# Pyr0-Piezo_Direct_Extruder_Board2_1_1.net
KiCad netlist of a schematic drawn in EAGLE
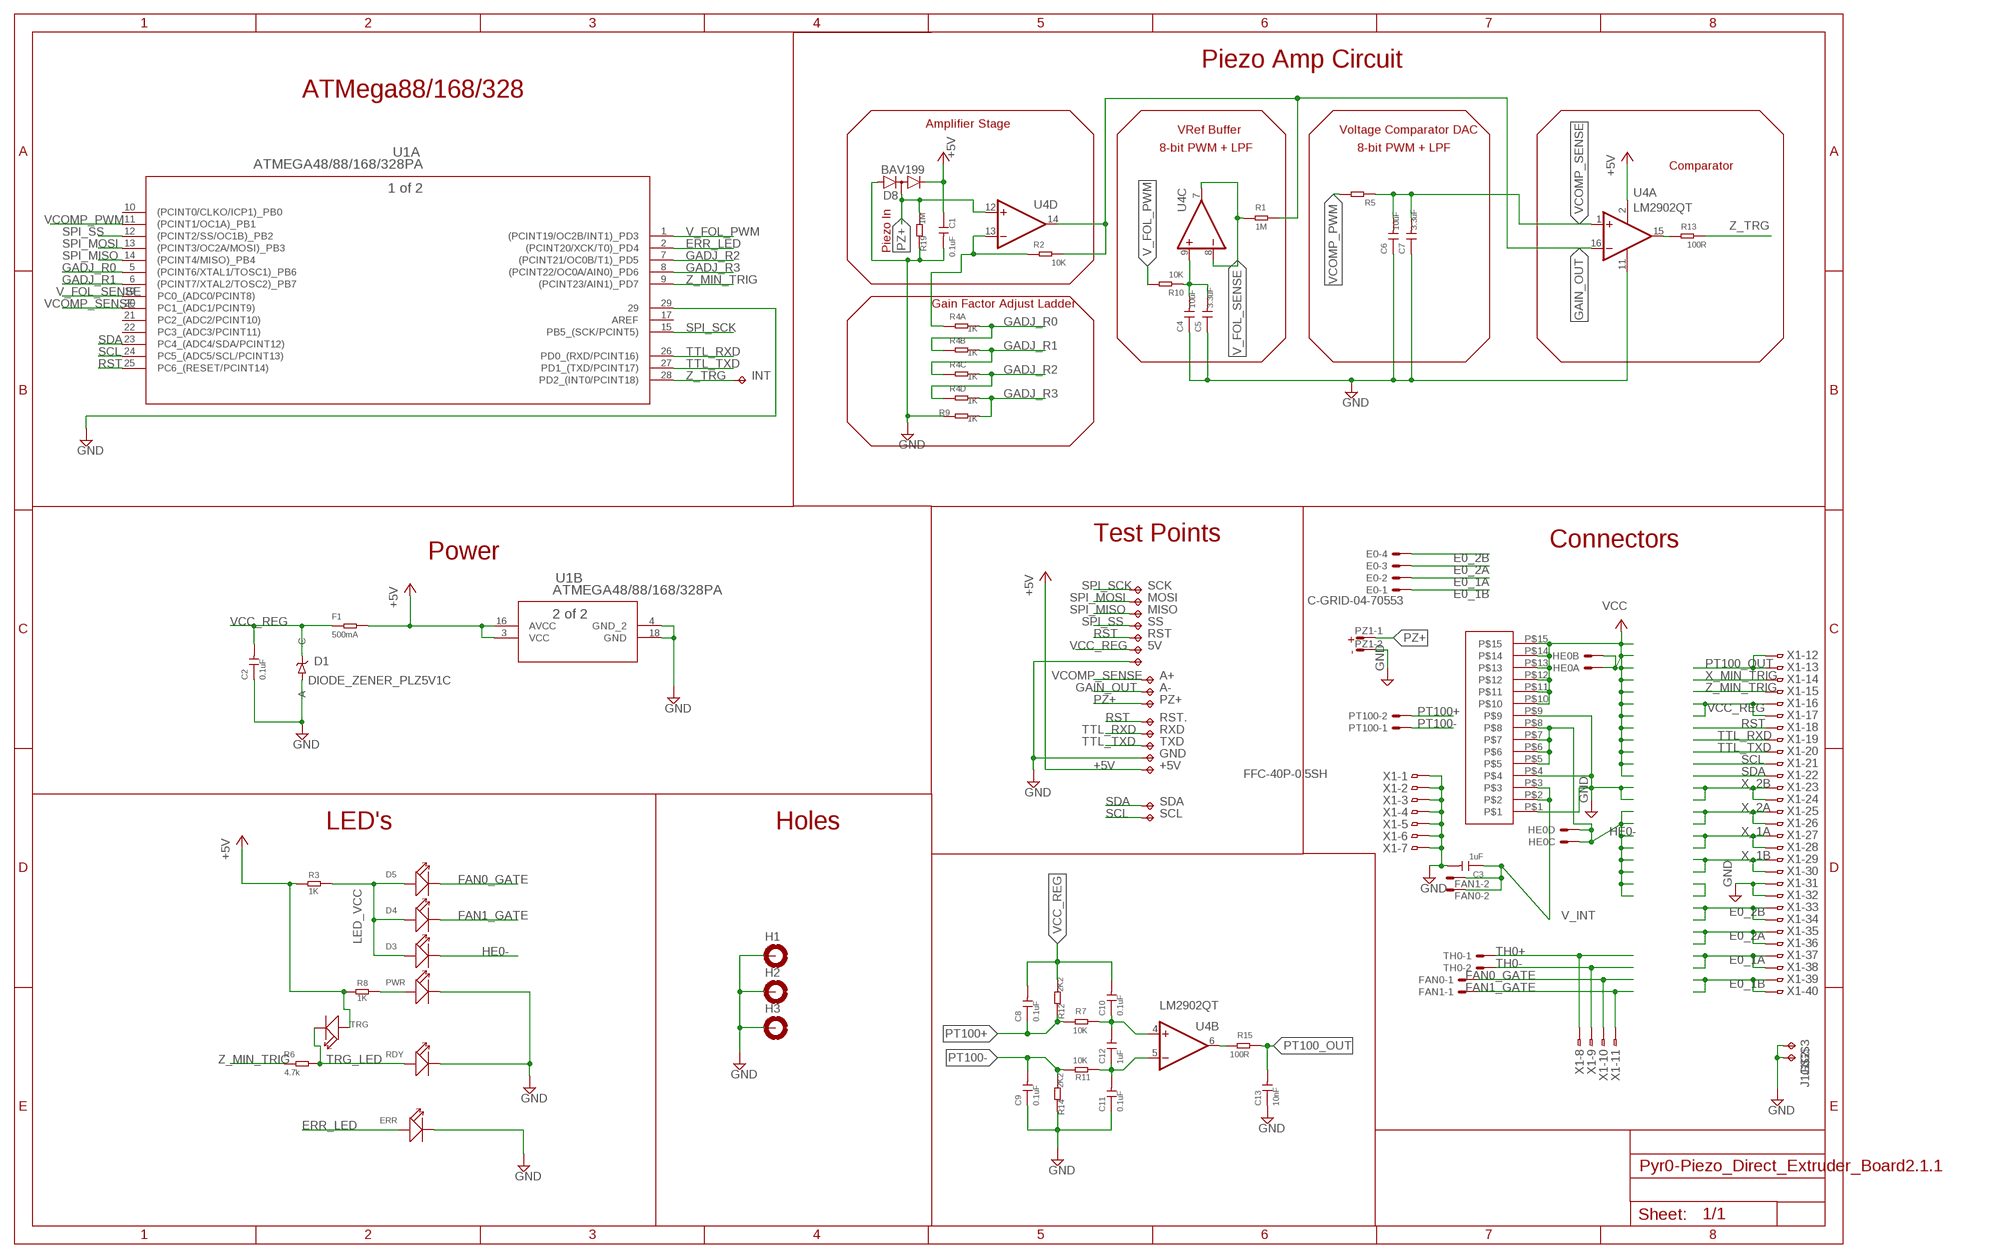
[diagram p0: schematic, sheet 1]

(export (version "E")
  (design (tool "Eeschema 10.0.6"))
  (components
    (comp (ref "+5V")
      (value "TPTP13SQ")
      (footprint "eagle-import:TP13SQ")
      (libsource (lib "eagle-import") (part "testpad_385_TPTP13SQ"))
    )
    (comp (ref "5V")
      (value "TPTP13SQ")
      (footprint "eagle-import:TP13SQ")
      (libsource (lib "eagle-import") (part "TPTP13SQ"))
    )
    (comp (ref "A+")
      (value "TPTP13SQ")
      (footprint "eagle-import:TP13SQ")
      (libsource (lib "eagle-import") (part "TPTP13SQ"))
    )
    (comp (ref "A-")
      (value "TPTP13SQ")
      (footprint "eagle-import:TP13SQ")
      (libsource (lib "eagle-import") (part "TPTP13SQ"))
    )
    (comp (ref "C1")
      (value "0.1uF")
      (footprint "eagle-import:CAPC1005X50")
      (libsource (lib "eagle-import") (part "CERAMIC-1NF-50V-10%-X7R(0402)CAP_0402"))
    )
    (comp (ref "C2")
      (value "0.1uF")
      (footprint "eagle-import:CAPC1005X50")
      (libsource (lib "eagle-import") (part "CERAMIC-1NF-50V-10%-X7R(0402)CAP_0402"))
    )
    (comp (ref "C3")
      (value "1uF")
      (footprint "eagle-import:CAPC1609X80")
      (libsource (lib "eagle-import") (part "SEEED-CAPACITOR_CERAMIC-10UF-25V-10%-X5R(0805)CAP_0603_GEN"))
    )
    (comp (ref "C4")
      (value "10uF")
      (footprint "eagle-import:CAPC1005X50")
      (libsource (lib "eagle-import") (part "CERAMIC-1NF-50V-10%-X7R(0402)CAP_0402"))
    )
    (comp (ref "C5")
      (value "3.3uF")
      (footprint "eagle-import:CAPC1609X80")
      (libsource (lib "eagle-import") (part "SEEED-CAPACITOR_CERAMIC-10UF-25V-10%-X5R(0805)CAP_0603_GEN"))
    )
    (comp (ref "C6")
      (value "10uF")
      (footprint "eagle-import:CAPC1005X50")
      (libsource (lib "eagle-import") (part "CERAMIC-1NF-50V-10%-X7R(0402)CAP_0402"))
    )
    (comp (ref "C7")
      (value "3.3uF")
      (footprint "eagle-import:CAPC1609X80")
      (libsource (lib "eagle-import") (part "SEEED-CAPACITOR_CERAMIC-10UF-25V-10%-X5R(0805)CAP_0603_GEN"))
    )
    (comp (ref "C8")
      (value "0.1uF")
      (footprint "eagle-import:CAPC1005X50")
      (libsource (lib "eagle-import") (part "CERAMIC-1NF-50V-10%-X7R(0402)CAP_0402"))
    )
    (comp (ref "C9")
      (value "0.1uF")
      (footprint "eagle-import:CAPC1005X50")
      (libsource (lib "eagle-import") (part "CERAMIC-1NF-50V-10%-X7R(0402)CAP_0402"))
    )
    (comp (ref "C10")
      (value "0.1uF")
      (footprint "eagle-import:CAPC1005X50")
      (libsource (lib "eagle-import") (part "CERAMIC-1NF-50V-10%-X7R(0402)CAP_0402"))
    )
    (comp (ref "C11")
      (value "0.1uF")
      (footprint "eagle-import:CAPC1005X50")
      (libsource (lib "eagle-import") (part "CERAMIC-1NF-50V-10%-X7R(0402)CAP_0402"))
    )
    (comp (ref "C12")
      (value "1uF")
      (footprint "eagle-import:CAPC1005X50")
      (libsource (lib "eagle-import") (part "CERAMIC-1NF-50V-10%-X7R(0402)CAP_0402"))
    )
    (comp (ref "C13")
      (value "10nF")
      (footprint "eagle-import:CAPC1005X50")
      (libsource (lib "eagle-import") (part "CERAMIC-1NF-50V-10%-X7R(0402)CAP_0402"))
    )
    (comp (ref "D1")
      (value "DIODE_ZENER_PLZ5V1C")
      (footprint "eagle-import:DO-219AC")
      (libsource (lib "eagle-import") (part "DIODE_ZENER_PLZ5V1C"))
    )
    (comp (ref "D3")
      (value "SEEED-LED_SMD-LED-CLEAR-BLUE(0603)LED_0603")
      (footprint "eagle-import:SEEED-LED_LED-0603")
      (libsource (lib "eagle-import") (part "SEEED-LED_SMD-LED-CLEAR-BLUE(0603)LED_0603"))
    )
    (comp (ref "D4")
      (value "SEEED-LED_SMD-LED-CLEAR-BLUE(0603)LED_0603")
      (footprint "eagle-import:SEEED-LED_LED-0603")
      (libsource (lib "eagle-import") (part "SEEED-LED_SMD-LED-CLEAR-BLUE(0603)LED_0603"))
    )
    (comp (ref "D5")
      (value "SEEED-LED_SMD-LED-CLEAR-BLUE(0603)LED_0603")
      (footprint "eagle-import:SEEED-LED_LED-0603")
      (libsource (lib "eagle-import") (part "SEEED-LED_SMD-LED-CLEAR-BLUE(0603)LED_0603"))
    )
    (comp (ref "D8")
      (value "BAV199")
      (footprint "eagle-import:SOT23")
      (libsource (lib "eagle-import") (part "BAV199"))
    )
    (comp (ref "E0")
      (value "C-GRID-04-70553")
      (footprint "eagle-import:70553-04")
      (fields (field (name "MF") "MOLEX"))
      (libsource (lib "eagle-import") (part "C-GRID-04-70553"))
    )
    (comp (ref "ERR")
      (value "SEEED-LED_SMD-LED-CLEAR-BLUE(0603)LED_0603")
      (footprint "eagle-import:SEEED-LED_LED-0603")
      (libsource (lib "eagle-import") (part "SEEED-LED_SMD-LED-CLEAR-BLUE(0603)LED_0603"))
    )
    (comp (ref "F1")
      (value "500mA")
      (footprint "eagle-import:SEEED-RESISTOR_R0603")
      (libsource (lib "eagle-import") (part "SEEED-RESISTOR_SMD-RES-1.5K-1%-1/10W(0603)DETAILED_MODEL"))
    )
    (comp (ref "FAN0")
      (value "CON-MOLEX-2P-1.27MM048")
      (footprint "eagle-import:53048-02")
      (fields (field (name "MF") "MOLEX") (field (name "MPN") "53048-0210"))
      (libsource (lib "eagle-import") (part "CON-MOLEX-2P-1.27MM048"))
    )
    (comp (ref "FAN1")
      (value "CON-MOLEX-2P-1.27MM048")
      (footprint "eagle-import:53048-02")
      (fields (field (name "MF") "MOLEX") (field (name "MPN") "53048-0210"))
      (libsource (lib "eagle-import") (part "CON-MOLEX-2P-1.27MM048"))
    )
    (comp (ref "GND")
      (value "TPTP13SQ")
      (footprint "eagle-import:TP13SQ")
      (libsource (lib "eagle-import") (part "testpad_385_TPTP13SQ"))
    )
    (comp (ref "H1")
      (value "HOLES_MOUNT-PAD-ROUND3.2")
      (footprint "eagle-import:HOLES_3,2-PAD")
      (libsource (lib "eagle-import") (part "HOLES_MOUNT-PAD-ROUND3.2"))
    )
    (comp (ref "H2")
      (value "HOLES_MOUNT-PAD-ROUND3.2")
      (footprint "eagle-import:HOLES_3,2-PAD")
      (libsource (lib "eagle-import") (part "HOLES_MOUNT-PAD-ROUND3.2"))
    )
    (comp (ref "H3")
      (value "HOLES_MOUNT-PAD-ROUND3.2")
      (footprint "eagle-import:HOLES_3,2-PAD")
      (libsource (lib "eagle-import") (part "HOLES_MOUNT-PAD-ROUND3.2"))
    )
    (comp (ref "HE0")
      (value "JST-2.54-2X2JST-DUPONT-2.54-2X2")
      (footprint "eagle-import:HDRRAR4W64P254_2X2_556X736X556B")
      (libsource (lib "eagle-import") (part "JST-2.54-2X2JST-DUPONT-2.54-2X2"))
    )
    (comp (ref "INT")
      (value "TPTP06R")
      (footprint "eagle-import:TP06R")
      (libsource (lib "eagle-import") (part "testpad_385_TPTP06R"))
    )
    (comp (ref "J1")
      (value "FFC-15P-1MM")
      (footprint "eagle-import:FFC-15P-1MM")
      (libsource (lib "eagle-import") (part "FFC-15P-1MM"))
    )
    (comp (ref "MISO")
      (value "TPTP13SQ")
      (footprint "eagle-import:TP13SQ")
      (libsource (lib "eagle-import") (part "TPTP13SQ"))
    )
    (comp (ref "MOSI")
      (value "TPTP13SQ")
      (footprint "eagle-import:TP13SQ")
      (libsource (lib "eagle-import") (part "TPTP13SQ"))
    )
    (comp (ref "PT100")
      (value "CON-MOLEX-2P-1.27MM048")
      (footprint "eagle-import:53048-02")
      (fields (field (name "MF") "MOLEX") (field (name "MPN") "53048-0210"))
      (libsource (lib "eagle-import") (part "CON-MOLEX-2P-1.27MM048"))
    )
    (comp (ref "PWR")
      (value "SEEED-LED_SMD-LED-CLEAR-BLUE(0603)LED_0603")
      (footprint "eagle-import:SEEED-LED_LED-0603")
      (libsource (lib "eagle-import") (part "SEEED-LED_SMD-LED-CLEAR-BLUE(0603)LED_0603"))
    )
    (comp (ref "PZ+")
      (value "TPTP13SQ")
      (footprint "eagle-import:TP13SQ")
      (libsource (lib "eagle-import") (part "TPTP13SQ"))
    )
    (comp (ref "PZ1")
      (value "CON-MOLEX-2P-1.27MM048")
      (footprint "eagle-import:53048-02")
      (fields (field (name "MF") "MOLEX") (field (name "MPN") "53048-0210"))
      (libsource (lib "eagle-import") (part "CON-MOLEX-2P-1.27MM048"))
    )
    (comp (ref "R1")
      (value "1M")
      (footprint "eagle-import:R0402")
      (fields (field (name "MPN") "RC0402JR-070RL"))
      (libsource (lib "eagle-import") (part "SMD-RES-0R-5%-1/16W(0402)"))
    )
    (comp (ref "R2")
      (value "10K")
      (footprint "eagle-import:R0402")
      (fields (field (name "MPN") "RC0402JR-070RL"))
      (libsource (lib "eagle-import") (part "SMD-RES-0R-5%-1/16W(0402)"))
    )
    (comp (ref "R3")
      (value "1K")
      (footprint "eagle-import:R0402")
      (fields (field (name "MPN") "RC0402JR-070RL"))
      (libsource (lib "eagle-import") (part "SMD-RES-0R-5%-1/16W(0402)"))
    )
    (comp (ref "R4")
      (value "1K")
      (footprint "eagle-import:EXBN8V")
      (libsource (lib "eagle-import") (part "RESISTOR_NETWORK_X40804"))
    )
    (comp (ref "R5")
      (value "10K")
      (footprint "eagle-import:SEEED-RESISTOR_R0603")
      (libsource (lib "eagle-import") (part "SEEED-RESISTOR_SMD-RES-1.5K-1%-1/10W(0603)DETAILED_MODEL"))
    )
    (comp (ref "R6")
      (value "4.7k")
      (footprint "eagle-import:R0402")
      (fields (field (name "MPN") "RC0402JR-070RL"))
      (libsource (lib "eagle-import") (part "SMD-RES-0R-5%-1/16W(0402)"))
    )
    (comp (ref "R7")
      (value "10K")
      (footprint "eagle-import:R0402")
      (fields (field (name "MPN") "RC0402JR-070RL"))
      (libsource (lib "eagle-import") (part "SMD-RES-0R-5%-1/16W(0402)"))
    )
    (comp (ref "R8")
      (value "1K")
      (footprint "eagle-import:R0402")
      (fields (field (name "MPN") "RC0402JR-070RL"))
      (libsource (lib "eagle-import") (part "SMD-RES-0R-5%-1/16W(0402)"))
    )
    (comp (ref "R9")
      (value "1K")
      (footprint "eagle-import:R0402")
      (fields (field (name "MPN") "RC0402JR-070RL"))
      (libsource (lib "eagle-import") (part "SMD-RES-0R-5%-1/16W(0402)"))
    )
    (comp (ref "R10")
      (value "10K")
      (footprint "eagle-import:R0402")
      (fields (field (name "MPN") "RC0402JR-070RL"))
      (libsource (lib "eagle-import") (part "SMD-RES-0R-5%-1/16W(0402)"))
    )
    (comp (ref "R11")
      (value "10K")
      (footprint "eagle-import:R0402")
      (fields (field (name "MPN") "RC0402JR-070RL"))
      (libsource (lib "eagle-import") (part "SMD-RES-0R-5%-1/16W(0402)"))
    )
    (comp (ref "R12")
      (value "2K2")
      (footprint "eagle-import:R0402")
      (fields (field (name "MPN") "RC0402JR-070RL"))
      (libsource (lib "eagle-import") (part "SMD-RES-0R-5%-1/16W(0402)"))
    )
    (comp (ref "R13")
      (value "100R")
      (footprint "eagle-import:R0402")
      (fields (field (name "MPN") "RC0402JR-070RL"))
      (libsource (lib "eagle-import") (part "SMD-RES-0R-5%-1/16W(0402)"))
    )
    (comp (ref "R14")
      (value "2K2")
      (footprint "eagle-import:R0402")
      (fields (field (name "MPN") "RC0402JR-070RL"))
      (libsource (lib "eagle-import") (part "SMD-RES-0R-5%-1/16W(0402)"))
    )
    (comp (ref "R15")
      (value "100R")
      (footprint "eagle-import:R0402")
      (fields (field (name "MPN") "RC0402JR-070RL"))
      (libsource (lib "eagle-import") (part "SMD-RES-0R-5%-1/16W(0402)"))
    )
    (comp (ref "R19")
      (value "1M")
      (footprint "eagle-import:R0402")
      (fields (field (name "MPN") "RC0402JR-070RL"))
      (libsource (lib "eagle-import") (part "SMD-RES-0R-5%-1/16W(0402)"))
    )
    (comp (ref "RDY")
      (value "SEEED-LED_SMD-LED-CLEAR-BLUE(0603)LED_0603")
      (footprint "eagle-import:SEEED-LED_LED-0603")
      (libsource (lib "eagle-import") (part "SEEED-LED_SMD-LED-CLEAR-BLUE(0603)LED_0603"))
    )
    (comp (ref "RST")
      (value "TPTP13SQ")
      (footprint "eagle-import:TP13SQ")
      (libsource (lib "eagle-import") (part "TPTP13SQ"))
    )
    (comp (ref "RST.")
      (value "TPTP13SQ")
      (footprint "eagle-import:TP13SQ")
      (libsource (lib "eagle-import") (part "testpad_385_TPTP13SQ"))
    )
    (comp (ref "RXD")
      (value "TPTP13SQ")
      (footprint "eagle-import:TP13SQ")
      (libsource (lib "eagle-import") (part "testpad_385_TPTP13SQ"))
    )
    (comp (ref "SCK")
      (value "TPTP13SQ")
      (footprint "eagle-import:TP13SQ")
      (libsource (lib "eagle-import") (part "TPTP13SQ"))
    )
    (comp (ref "SCL")
      (value "TPTP13SQ")
      (footprint "eagle-import:TP13SQ")
      (libsource (lib "eagle-import") (part "testpad_385_TPTP13SQ"))
    )
    (comp (ref "SDA")
      (value "TPTP13SQ")
      (footprint "eagle-import:TP13SQ")
      (libsource (lib "eagle-import") (part "testpad_385_TPTP13SQ"))
    )
    (comp (ref "SS")
      (value "TPTP06R")
      (footprint "eagle-import:TP06R")
      (libsource (lib "eagle-import") (part "testpad_385_TPTP06R"))
    )
    (comp (ref "TH0")
      (value "CON-MOLEX-2P-1.27MM048")
      (footprint "eagle-import:53048-02")
      (fields (field (name "MF") "MOLEX") (field (name "MPN") "53048-0210"))
      (libsource (lib "eagle-import") (part "CON-MOLEX-2P-1.27MM048"))
    )
    (comp (ref "TRG")
      (value "SEEED-LED_SMD-LED-CLEAR-BLUE(0603)LED_0603")
      (footprint "eagle-import:SEEED-LED_LED-0603")
      (libsource (lib "eagle-import") (part "SEEED-LED_SMD-LED-CLEAR-BLUE(0603)LED_0603"))
    )
    (comp (ref "TXD")
      (value "TPTP13SQ")
      (footprint "eagle-import:TP13SQ")
      (libsource (lib "eagle-import") (part "testpad_385_TPTP13SQ"))
    )
    (comp (ref "U1")
      (value "ATMEGA48/88/168/328PA")
      (footprint "eagle-import:28M1")
      (fields (field (name "MANUFACTURER_PART_NUMBER") "ATMEGA48PAMMHR"))
      (libsource (lib "eagle-import") (part "ATMEGA48/88/168/328PA"))
    )
    (comp (ref "U4")
      (value "LM2902QT")
      (footprint "eagle-import:QFN16")
      (libsource (lib "eagle-import") (part "LM2902QT"))
    )
    (comp (ref "X1")
      (value "FFC-40P-0.5SH")
      (footprint "eagle-import:FH12-40S-0.5SH")
      (fields (field (name "MPN") "FH12-40S-0.5SH(55)"))
      (libsource (lib "eagle-import") (part "FFC-40P-0.5SH"))
    )
    (comp (ref "⏚")
      (value "TPTP13SQ")
      (footprint "eagle-import:TP13SQ")
      (libsource (lib "eagle-import") (part "testpad_385_TPTP13SQ"))
    )
  )
  (nets
    (net (code "1") (name "+5V") (class "Default")
      (node (ref "+5V") (pin "TP") (pinfunction "TP_TP") (pintype "input"))
      (node (ref "C1") (pin "1") (pinfunction "1_1") (pintype "passive"))
      (node (ref "D8") (pin "2") (pinfunction "C_2") (pintype "passive"))
      (node (ref "F1") (pin "2") (pinfunction "2_2") (pintype "passive"))
      (node (ref "R3") (pin "1") (pinfunction "1_1") (pintype "passive"))
      (node (ref "R8") (pin "1") (pinfunction "1_1") (pintype "passive"))
      (node (ref "TRG") (pin "+") (pinfunction "+_+") (pintype "passive"))
      (node (ref "U1") (pin "16") (pinfunction "AVCC_16") (pintype "power_in"))
      (node (ref "U1") (pin "3") (pinfunction "VCC_3") (pintype "power_in"))
      (node (ref "U4") (pin "2") (pinfunction "V+_2") (pintype "power_in"))
    )
    (net (code "2") (name "/E0_1A") (class "Default")
      (node (ref "E0") (pin "2") (pinfunction "S_2") (pintype "passive"))
      (node (ref "X1") (pin "37") (pinfunction "1_37") (pintype "passive"))
      (node (ref "X1") (pin "38") (pinfunction "1_38") (pintype "passive"))
    )
    (net (code "3") (name "/E0_1B") (class "Default")
      (node (ref "E0") (pin "1") (pinfunction "S_1") (pintype "passive"))
      (node (ref "X1") (pin "39") (pinfunction "1_39") (pintype "passive"))
      (node (ref "X1") (pin "40") (pinfunction "1_40") (pintype "passive"))
    )
    (net (code "4") (name "/E0_2A") (class "Default")
      (node (ref "E0") (pin "3") (pinfunction "S_3") (pintype "passive"))
      (node (ref "X1") (pin "35") (pinfunction "1_35") (pintype "passive"))
      (node (ref "X1") (pin "36") (pinfunction "1_36") (pintype "passive"))
    )
    (net (code "5") (name "/E0_2B") (class "Default")
      (node (ref "E0") (pin "4") (pinfunction "S_4") (pintype "passive"))
      (node (ref "X1") (pin "33") (pinfunction "1_33") (pintype "passive"))
      (node (ref "X1") (pin "34") (pinfunction "1_34") (pintype "passive"))
    )
    (net (code "6") (name "/ERR_LED") (class "Default")
      (node (ref "ERR") (pin "+") (pinfunction "+_+") (pintype "passive"))
      (node (ref "U1") (pin "2") (pinfunction "(PCINT20/XCK/T0)_PD4_2") (pintype "bidirectional"))
    )
    (net (code "7") (name "/FAN0_GATE") (class "Default")
      (node (ref "D5") (pin "-") (pinfunction "-_-") (pintype "passive"))
      (node (ref "FAN0") (pin "1") (pinfunction "S_1") (pintype "passive"))
      (node (ref "X1") (pin "10") (pinfunction "1_10") (pintype "passive"))
    )
    (net (code "8") (name "/FAN1_GATE") (class "Default")
      (node (ref "D4") (pin "-") (pinfunction "-_-") (pintype "passive"))
      (node (ref "FAN1") (pin "1") (pinfunction "S_1") (pintype "passive"))
      (node (ref "X1") (pin "11") (pinfunction "1_11") (pintype "passive"))
    )
    (net (code "9") (name "/GADJ_R0") (class "Default")
      (node (ref "R4") (pin "2") (pinfunction "1_2") (pintype "passive"))
      (node (ref "R4") (pin "8") (pinfunction "2_8") (pintype "passive"))
      (node (ref "U1") (pin "5") (pinfunction "(PCINT6/XTAL1/TOSC1)_PB6_5") (pintype "bidirectional"))
    )
    (net (code "10") (name "/GADJ_R1") (class "Default")
      (node (ref "R4") (pin "3") (pinfunction "1_3") (pintype "passive"))
      (node (ref "R4") (pin "7") (pinfunction "2_7") (pintype "passive"))
      (node (ref "U1") (pin "6") (pinfunction "(PCINT7/XTAL2/TOSC2)_PB7_6") (pintype "bidirectional"))
    )
    (net (code "11") (name "/GADJ_R2") (class "Default")
      (node (ref "R4") (pin "4") (pinfunction "1_4") (pintype "passive"))
      (node (ref "R4") (pin "6") (pinfunction "2_6") (pintype "passive"))
      (node (ref "U1") (pin "7") (pinfunction "(PCINT21/OC0B/T1)_PD5_7") (pintype "bidirectional"))
    )
    (net (code "12") (name "/GADJ_R3") (class "Default")
      (node (ref "R4") (pin "5") (pinfunction "2_5") (pintype "passive"))
      (node (ref "R9") (pin "2") (pinfunction "2_2") (pintype "passive"))
      (node (ref "U1") (pin "8") (pinfunction "(PCINT22/OC0A/AIN0)_PD6_8") (pintype "bidirectional"))
    )
    (net (code "13") (name "/HE0-") (class "Default")
      (node (ref "D3") (pin "-") (pinfunction "-_-") (pintype "passive"))
      (node (ref "HE0") (pin "3") (pinfunction "S_3") (pintype "passive"))
      (node (ref "HE0") (pin "4") (pinfunction "S_4") (pintype "passive"))
      (node (ref "J1") (pin "P$5") (pinfunction "P$5_P$5") (pintype "bidirectional"))
      (node (ref "J1") (pin "P$6") (pinfunction "P$6_P$6") (pintype "bidirectional"))
      (node (ref "J1") (pin "P$7") (pinfunction "P$7_P$7") (pintype "bidirectional"))
      (node (ref "J1") (pin "P$8") (pinfunction "P$8_P$8") (pintype "bidirectional"))
    )
    (net (code "14") (name "/LED_VCC") (class "Default")
      (node (ref "D3") (pin "+") (pinfunction "+_+") (pintype "passive"))
      (node (ref "D4") (pin "+") (pinfunction "+_+") (pintype "passive"))
      (node (ref "D5") (pin "+") (pinfunction "+_+") (pintype "passive"))
      (node (ref "R3") (pin "2") (pinfunction "2_2") (pintype "passive"))
    )
    (net (code "15") (name "/RST") (class "Default")
      (node (ref "RST") (pin "TP") (pinfunction "TP_TP") (pintype "input"))
      (node (ref "RST.") (pin "TP") (pinfunction "TP_TP") (pintype "input"))
      (node (ref "U1") (pin "25") (pinfunction "PC6_(RESET/PCINT14)_25") (pintype "bidirectional"))
      (node (ref "X1") (pin "18") (pinfunction "1_18") (pintype "passive"))
    )
    (net (code "16") (name "/SCL") (class "Default")
      (node (ref "SCL") (pin "TP") (pinfunction "TP_TP") (pintype "input"))
      (node (ref "U1") (pin "24") (pinfunction "PC5_(ADC5/SCL/PCINT13)_24") (pintype "bidirectional"))
      (node (ref "X1") (pin "21") (pinfunction "1_21") (pintype "passive"))
    )
    (net (code "17") (name "/SDA") (class "Default")
      (node (ref "SDA") (pin "TP") (pinfunction "TP_TP") (pintype "input"))
      (node (ref "U1") (pin "23") (pinfunction "PC4_(ADC4/SDA/PCINT12)_23") (pintype "bidirectional"))
      (node (ref "X1") (pin "22") (pinfunction "1_22") (pintype "passive"))
    )
    (net (code "18") (name "/SPI_MISO") (class "Default")
      (node (ref "MISO") (pin "TP") (pinfunction "TP_TP") (pintype "input"))
      (node (ref "U1") (pin "14") (pinfunction "(PCINT4/MISO)_PB4_14") (pintype "bidirectional"))
    )
    (net (code "19") (name "/SPI_MOSI") (class "Default")
      (node (ref "MOSI") (pin "TP") (pinfunction "TP_TP") (pintype "input"))
      (node (ref "U1") (pin "13") (pinfunction "(PCINT3/OC2A/MOSI)_PB3_13") (pintype "bidirectional"))
    )
    (net (code "20") (name "/SPI_SCK") (class "Default")
      (node (ref "SCK") (pin "TP") (pinfunction "TP_TP") (pintype "input"))
      (node (ref "U1") (pin "15") (pinfunction "PB5_(SCK/PCINT5)_15") (pintype "bidirectional"))
    )
    (net (code "21") (name "/SPI_SS") (class "Default")
      (node (ref "SS") (pin "TP") (pinfunction "TP_TP") (pintype "input"))
      (node (ref "U1") (pin "12") (pinfunction "(PCINT2/SS/OC1B)_PB2_12") (pintype "bidirectional"))
    )
    (net (code "22") (name "/TH0+") (class "Default")
      (node (ref "TH0") (pin "1") (pinfunction "S_1") (pintype "passive"))
      (node (ref "X1") (pin "8") (pinfunction "1_8") (pintype "passive"))
    )
    (net (code "23") (name "/TH0-") (class "Default")
      (node (ref "TH0") (pin "2") (pinfunction "S_2") (pintype "passive"))
      (node (ref "X1") (pin "9") (pinfunction "1_9") (pintype "passive"))
    )
    (net (code "24") (name "/TRG_LED") (class "Default")
      (node (ref "R6") (pin "2") (pinfunction "2_2") (pintype "passive"))
      (node (ref "RDY") (pin "+") (pinfunction "+_+") (pintype "passive"))
      (node (ref "TRG") (pin "-") (pinfunction "-_-") (pintype "passive"))
    )
    (net (code "25") (name "/TTL_RXD") (class "Default")
      (node (ref "RXD") (pin "TP") (pinfunction "TP_TP") (pintype "input"))
      (node (ref "U1") (pin "26") (pinfunction "PD0_(RXD/PCINT16)_26") (pintype "bidirectional"))
      (node (ref "X1") (pin "19") (pinfunction "1_19") (pintype "passive"))
    )
    (net (code "26") (name "/TTL_TXD") (class "Default")
      (node (ref "TXD") (pin "TP") (pinfunction "TP_TP") (pintype "input"))
      (node (ref "U1") (pin "27") (pinfunction "PD1_(TXD/PCINT17)_27") (pintype "bidirectional"))
      (node (ref "X1") (pin "20") (pinfunction "1_20") (pintype "passive"))
    )
    (net (code "27") (name "/V_INT") (class "Default")
      (node (ref "C3") (pin "1") (pinfunction "1_1") (pintype "passive"))
      (node (ref "FAN0") (pin "2") (pinfunction "S_2") (pintype "passive"))
      (node (ref "FAN1") (pin "2") (pinfunction "S_2") (pintype "passive"))
      (node (ref "J1") (pin "P$2") (pinfunction "P$2_P$2") (pintype "bidirectional"))
      (node (ref "J1") (pin "P$3") (pinfunction "P$3_P$3") (pintype "bidirectional"))
    )
    (net (code "28") (name "/X_1A") (class "Default")
      (node (ref "X1") (pin "27") (pinfunction "1_27") (pintype "passive"))
      (node (ref "X1") (pin "28") (pinfunction "1_28") (pintype "passive"))
    )
    (net (code "29") (name "/X_1B") (class "Default")
      (node (ref "X1") (pin "29") (pinfunction "1_29") (pintype "passive"))
      (node (ref "X1") (pin "30") (pinfunction "1_30") (pintype "passive"))
    )
    (net (code "30") (name "/X_2A") (class "Default")
      (node (ref "X1") (pin "25") (pinfunction "1_25") (pintype "passive"))
      (node (ref "X1") (pin "26") (pinfunction "1_26") (pintype "passive"))
    )
    (net (code "31") (name "/X_2B") (class "Default")
      (node (ref "X1") (pin "23") (pinfunction "1_23") (pintype "passive"))
      (node (ref "X1") (pin "24") (pinfunction "1_24") (pintype "passive"))
    )
    (net (code "32") (name "/X_MIN_TRIG") (class "Default")
      (node (ref "X1") (pin "14") (pinfunction "1_14") (pintype "passive"))
    )
    (net (code "33") (name "/Z_MIN_TRIG") (class "Default")
      (node (ref "R6") (pin "1") (pinfunction "1_1") (pintype "passive"))
      (node (ref "U1") (pin "9") (pinfunction "(PCINT23/AIN1)_PD7_9") (pintype "bidirectional"))
      (node (ref "X1") (pin "15") (pinfunction "1_15") (pintype "passive"))
    )
    (net (code "34") (name "/Z_TRG") (class "Default")
      (node (ref "INT") (pin "TP") (pinfunction "TP_TP") (pintype "input"))
      (node (ref "R13") (pin "2") (pinfunction "2_2") (pintype "passive"))
      (node (ref "U1") (pin "28") (pinfunction "PD2_(INT0/PCINT18)_28") (pintype "bidirectional"))
    )
    (net (code "35") (name "GAIN_OUT") (class "Default")
      (node (ref "A-") (pin "TP") (pinfunction "TP_TP") (pintype "input"))
      (node (ref "R1") (pin "2") (pinfunction "2_2") (pintype "passive"))
      (node (ref "R2") (pin "2") (pinfunction "2_2") (pintype "passive"))
      (node (ref "U4") (pin "14") (pinfunction "OUT_14") (pintype "output"))
      (node (ref "U4") (pin "16") (pinfunction "-IN_16") (pintype "input"))
    )
    (net (code "36") (name "GND") (class "Default")
      (node (ref "C1") (pin "2") (pinfunction "2_2") (pintype "passive"))
      (node (ref "C11") (pin "1") (pinfunction "1_1") (pintype "passive"))
      (node (ref "C13") (pin "1") (pinfunction "1_1") (pintype "passive"))
      (node (ref "C2") (pin "1") (pinfunction "1_1") (pintype "passive"))
      (node (ref "C3") (pin "2") (pinfunction "2_2") (pintype "passive"))
      (node (ref "C4") (pin "1") (pinfunction "1_1") (pintype "passive"))
      (node (ref "C5") (pin "1") (pinfunction "1_1") (pintype "passive"))
      (node (ref "C6") (pin "1") (pinfunction "1_1") (pintype "passive"))
      (node (ref "C7") (pin "1") (pinfunction "1_1") (pintype "passive"))
      (node (ref "C9") (pin "1") (pinfunction "1_1") (pintype "passive"))
      (node (ref "D1") (pin "P$1") (pinfunction "A_P$1") (pintype "passive"))
      (node (ref "D8") (pin "1") (pinfunction "A_1") (pintype "passive"))
      (node (ref "ERR") (pin "-") (pinfunction "-_-") (pintype "passive"))
      (node (ref "GND") (pin "TP") (pinfunction "TP_TP") (pintype "input"))
      (node (ref "H1") (pin "B3,2") (pinfunction "MOUNT_B3,2") (pintype "passive"))
      (node (ref "H2") (pin "B3,2") (pinfunction "MOUNT_B3,2") (pintype "passive"))
      (node (ref "H3") (pin "B3,2") (pinfunction "MOUNT_B3,2") (pintype "passive"))
      (node (ref "J1") (pin "P$1") (pinfunction "P$1_P$1") (pintype "bidirectional"))
      (node (ref "J1") (pin "P$16") (pinfunction "TP_P$16") (pintype "input"))
      (node (ref "J1") (pin "P$17") (pinfunction "TP_P$17") (pintype "input"))
      (node (ref "J1") (pin "P$4") (pinfunction "P$4_P$4") (pintype "bidirectional"))
      (node (ref "J1") (pin "P$9") (pinfunction "P$9_P$9") (pintype "bidirectional"))
      (node (ref "PWR") (pin "-") (pinfunction "-_-") (pintype "passive"))
      (node (ref "PZ1") (pin "2") (pinfunction "S_2") (pintype "passive"))
      (node (ref "R14") (pin "1") (pinfunction "1_1") (pintype "passive"))
      (node (ref "R19") (pin "1") (pinfunction "1_1") (pintype "passive"))
      (node (ref "R9") (pin "1") (pinfunction "1_1") (pintype "passive"))
      (node (ref "RDY") (pin "-") (pinfunction "-_-") (pintype "passive"))
      (node (ref "U1") (pin "18") (pinfunction "GND_18") (pintype "power_in"))
      (node (ref "U1") (pin "29") (pinfunction "29_29") (pintype "passive"))
      (node (ref "U1") (pin "4") (pinfunction "GND_2_4") (pintype "power_in"))
      (node (ref "U4") (pin "11") (pinfunction "V-_11") (pintype "power_in"))
      (node (ref "X1") (pin "1") (pinfunction "1_1") (pintype "passive"))
      (node (ref "X1") (pin "2") (pinfunction "1_2") (pintype "passive"))
      (node (ref "X1") (pin "3") (pinfunction "1_3") (pintype "passive"))
      (node (ref "X1") (pin "31") (pinfunction "1_31") (pintype "passive"))
      (node (ref "X1") (pin "32") (pinfunction "1_32") (pintype "passive"))
      (node (ref "X1") (pin "4") (pinfunction "1_4") (pintype "passive"))
      (node (ref "X1") (pin "5") (pinfunction "1_5") (pintype "passive"))
      (node (ref "X1") (pin "6") (pinfunction "1_6") (pintype "passive"))
      (node (ref "X1") (pin "7") (pinfunction "1_7") (pintype "passive"))
      (node (ref "⏚") (pin "TP") (pinfunction "TP_TP") (pintype "input"))
    )
    (net (code "37") (name "Net-(PWR-Pad+)") (class "Default")
      (node (ref "PWR") (pin "+") (pinfunction "+_+") (pintype "passive"))
      (node (ref "R8") (pin "2") (pinfunction "2_2") (pintype "passive"))
    )
    (net (code "38") (name "Net-(U4A-OUT)") (class "Default")
      (node (ref "R13") (pin "1") (pinfunction "1_1") (pintype "passive"))
      (node (ref "U4") (pin "15") (pinfunction "OUT_15") (pintype "output"))
    )
    (net (code "39") (name "Net-(U4B-+IN)") (class "Default")
      (node (ref "C10") (pin "1") (pinfunction "1_1") (pintype "passive"))
      (node (ref "C12") (pin "2") (pinfunction "2_2") (pintype "passive"))
      (node (ref "R7") (pin "1") (pinfunction "1_1") (pintype "passive"))
      (node (ref "U4") (pin "4") (pinfunction "+IN_4") (pintype "input"))
    )
    (net (code "40") (name "Net-(U4B--IN)") (class "Default")
      (node (ref "C11") (pin "2") (pinfunction "2_2") (pintype "passive"))
      (node (ref "C12") (pin "1") (pinfunction "1_1") (pintype "passive"))
      (node (ref "R11") (pin "1") (pinfunction "1_1") (pintype "passive"))
      (node (ref "U4") (pin "5") (pinfunction "-IN_5") (pintype "input"))
    )
    (net (code "41") (name "Net-(U4B-OUT)") (class "Default")
      (node (ref "R15") (pin "2") (pinfunction "2_2") (pintype "passive"))
      (node (ref "U4") (pin "6") (pinfunction "OUT_6") (pintype "output"))
    )
    (net (code "42") (name "Net-(U4C-+IN)") (class "Default")
      (node (ref "C4") (pin "2") (pinfunction "2_2") (pintype "passive"))
      (node (ref "C5") (pin "2") (pinfunction "2_2") (pintype "passive"))
      (node (ref "R10") (pin "1") (pinfunction "1_1") (pintype "passive"))
      (node (ref "U4") (pin "9") (pinfunction "+IN_9") (pintype "input"))
    )
    (net (code "43") (name "Net-(U4D--IN)") (class "Default")
      (node (ref "R2") (pin "1") (pinfunction "1_1") (pintype "passive"))
      (node (ref "R4") (pin "1") (pinfunction "1_1") (pintype "passive"))
      (node (ref "U4") (pin "13") (pinfunction "-IN_13") (pintype "input"))
    )
    (net (code "44") (name "PT100+") (class "Default")
      (node (ref "C8") (pin "1") (pinfunction "1_1") (pintype "passive"))
      (node (ref "PT100") (pin "2") (pinfunction "S_2") (pintype "passive"))
      (node (ref "R12") (pin "1") (pinfunction "1_1") (pintype "passive"))
      (node (ref "R7") (pin "2") (pinfunction "2_2") (pintype "passive"))
    )
    (net (code "45") (name "PT100-") (class "Default")
      (node (ref "C9") (pin "2") (pinfunction "2_2") (pintype "passive"))
      (node (ref "PT100") (pin "1") (pinfunction "S_1") (pintype "passive"))
      (node (ref "R11") (pin "2") (pinfunction "2_2") (pintype "passive"))
      (node (ref "R14") (pin "2") (pinfunction "2_2") (pintype "passive"))
    )
    (net (code "46") (name "PT100_OUT") (class "Default")
      (node (ref "C13") (pin "2") (pinfunction "2_2") (pintype "passive"))
      (node (ref "R15") (pin "1") (pinfunction "1_1") (pintype "passive"))
      (node (ref "X1") (pin "12") (pinfunction "1_12") (pintype "passive"))
      (node (ref "X1") (pin "13") (pinfunction "1_13") (pintype "passive"))
    )
    (net (code "47") (name "PZ+") (class "Default")
      (node (ref "D8") (pin "3") (pinfunction "AC_3") (pintype "passive"))
      (node (ref "PZ+") (pin "TP") (pinfunction "TP_TP") (pintype "input"))
      (node (ref "PZ1") (pin "1") (pinfunction "S_1") (pintype "passive"))
      (node (ref "R19") (pin "2") (pinfunction "2_2") (pintype "passive"))
      (node (ref "U4") (pin "12") (pinfunction "+IN_12") (pintype "input"))
    )
    (net (code "48") (name "VCC") (class "Default")
      (node (ref "HE0") (pin "1") (pinfunction "S_1") (pintype "passive"))
      (node (ref "HE0") (pin "2") (pinfunction "S_2") (pintype "passive"))
      (node (ref "J1") (pin "P$10") (pinfunction "P$10_P$10") (pintype "bidirectional"))
      (node (ref "J1") (pin "P$11") (pinfunction "P$11_P$11") (pintype "bidirectional"))
      (node (ref "J1") (pin "P$12") (pinfunction "P$12_P$12") (pintype "bidirectional"))
      (node (ref "J1") (pin "P$13") (pinfunction "P$13_P$13") (pintype "bidirectional"))
      (node (ref "J1") (pin "P$14") (pinfunction "P$14_P$14") (pintype "bidirectional"))
      (node (ref "J1") (pin "P$15") (pinfunction "P$15_P$15") (pintype "bidirectional"))
    )
    (net (code "49") (name "VCC_REG") (class "Default")
      (node (ref "5V") (pin "TP") (pinfunction "TP_TP") (pintype "input"))
      (node (ref "C10") (pin "2") (pinfunction "2_2") (pintype "passive"))
      (node (ref "C2") (pin "2") (pinfunction "2_2") (pintype "passive"))
      (node (ref "C8") (pin "2") (pinfunction "2_2") (pintype "passive"))
      (node (ref "D1") (pin "P$2") (pinfunction "C_P$2") (pintype "passive"))
      (node (ref "F1") (pin "1") (pinfunction "1_1") (pintype "passive"))
      (node (ref "R12") (pin "2") (pinfunction "2_2") (pintype "passive"))
      (node (ref "X1") (pin "16") (pinfunction "1_16") (pintype "passive"))
      (node (ref "X1") (pin "17") (pinfunction "1_17") (pintype "passive"))
    )
    (net (code "50") (name "VCOMP_PWM") (class "Default")
      (node (ref "R5") (pin "2") (pinfunction "2_2") (pintype "passive"))
      (node (ref "U1") (pin "11") (pinfunction "(PCINT1/OC1A)_PB1_11") (pintype "bidirectional"))
    )
    (net (code "51") (name "VCOMP_SENSE") (class "Default")
      (node (ref "A+") (pin "TP") (pinfunction "TP_TP") (pintype "input"))
      (node (ref "C6") (pin "2") (pinfunction "2_2") (pintype "passive"))
      (node (ref "C7") (pin "2") (pinfunction "2_2") (pintype "passive"))
      (node (ref "R5") (pin "1") (pinfunction "1_1") (pintype "passive"))
      (node (ref "U1") (pin "20") (pinfunction "PC1_(ADC1/PCINT9)_20") (pintype "bidirectional"))
      (node (ref "U4") (pin "1") (pinfunction "+IN_1") (pintype "input"))
    )
    (net (code "52") (name "V_FOL_PWM") (class "Default")
      (node (ref "R10") (pin "2") (pinfunction "2_2") (pintype "passive"))
      (node (ref "U1") (pin "1") (pinfunction "(PCINT19/OC2B/INT1)_PD3_1") (pintype "bidirectional"))
    )
    (net (code "53") (name "V_FOL_SENSE") (class "Default")
      (node (ref "R1") (pin "1") (pinfunction "1_1") (pintype "passive"))
      (node (ref "U1") (pin "19") (pinfunction "PC0_(ADC0/PCINT8)_19") (pintype "bidirectional"))
      (node (ref "U4") (pin "7") (pinfunction "OUT_7") (pintype "output"))
      (node (ref "U4") (pin "8") (pinfunction "-IN_8") (pintype "input"))
    )
    (net (code "54") (name "unconnected-(U1A-(PCINT0{slash}CLKO{slash}ICP1)_PB0-Pad10)") (class "Default")
      (node (ref "U1") (pin "10") (pinfunction "(PCINT0/CLKO/ICP1)_PB0_10") (pintype "bidirectional"))
    )
    (net (code "55") (name "unconnected-(U1A-AREF-Pad17)") (class "Default")
      (node (ref "U1") (pin "17") (pinfunction "AREF_17") (pintype "passive"))
    )
    (net (code "56") (name "unconnected-(U1A-PC2_(ADC2{slash}PCINT10)-Pad21)") (class "Default")
      (node (ref "U1") (pin "21") (pinfunction "PC2_(ADC2/PCINT10)_21") (pintype "bidirectional"))
    )
    (net (code "57") (name "unconnected-(U1A-PC3_(ADC3{slash}PCINT11)-Pad22)") (class "Default")
      (node (ref "U1") (pin "22") (pinfunction "PC3_(ADC3/PCINT11)_22") (pintype "bidirectional"))
    )
  )
)
